# LED.net
KiCad netlist of a schematic drawn in EAGLE
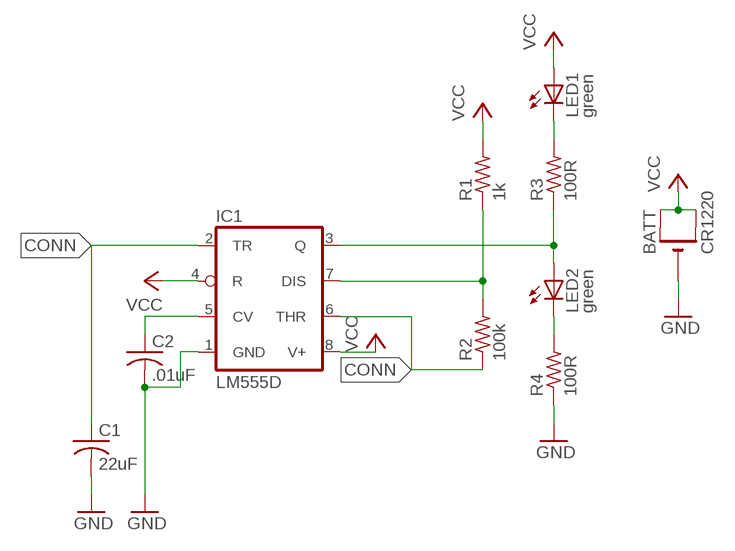
[diagram p0: schematic, sheet 1]

(export (version "E")
  (design (tool "Eeschema 10.0.6"))
  (components
    (comp (ref "BATT")
      (value "CR1220")
      (footprint "eagle-import:CR1220-SMD")
      (libsource (lib "eagle-import") (part "CR1220SMT"))
    )
    (comp (ref "C1")
      (value "22uF")
      (footprint "eagle-import:C0805")
      (fields (field (name "SPICEPREFIX") "C"))
      (libsource (lib "eagle-import") (part "C-USC0805"))
    )
    (comp (ref "C2")
      (value ".01uF")
      (footprint "eagle-import:C0805")
      (libsource (lib "eagle-import") (part "C-USC0805"))
    )
    (comp (ref "IC1")
      (value "LM555D")
      (footprint "eagle-import:SO08")
      (fields (field (name "SPICEPREFIX") "X"))
      (libsource (lib "eagle-import") (part "555DLM"))
    )
    (comp (ref "LED1")
      (value "green")
      (footprint "eagle-import:CHIPLED_0805")
      (libsource (lib "eagle-import") (part "LEDCHIPLED_0805"))
    )
    (comp (ref "LED2")
      (value "green")
      (footprint "eagle-import:CHIPLED_0805")
      (libsource (lib "eagle-import") (part "LEDCHIPLED_0805"))
    )
    (comp (ref "R1")
      (value "1k")
      (footprint "eagle-import:R0805")
      (libsource (lib "eagle-import") (part "R-US_R0805"))
    )
    (comp (ref "R2")
      (value "100k")
      (footprint "eagle-import:R0805")
      (libsource (lib "eagle-import") (part "R-US_R0805"))
    )
    (comp (ref "R3")
      (value "100R")
      (footprint "eagle-import:R0805")
      (libsource (lib "eagle-import") (part "R-US_R0805"))
    )
    (comp (ref "R4")
      (value "100R")
      (footprint "eagle-import:R0805")
      (libsource (lib "eagle-import") (part "R-US_R0805"))
    )
  )
  (nets
    (net (code "1") (name "CONN") (class "Default")
      (node (ref "C1") (pin "1") (pinfunction "1_1") (pintype "passive"))
      (node (ref "IC1") (pin "2") (pinfunction "TR_2") (pintype "input"))
      (node (ref "IC1") (pin "6") (pinfunction "THR_6") (pintype "input"))
      (node (ref "R2") (pin "1") (pinfunction "1_1") (pintype "passive"))
    )
    (net (code "2") (name "GND") (class "Default")
      (node (ref "BATT") (pin "-") (pinfunction "-_-") (pintype "passive"))
      (node (ref "C1") (pin "2") (pinfunction "2_2") (pintype "passive"))
      (node (ref "C2") (pin "2") (pinfunction "2_2") (pintype "passive"))
      (node (ref "IC1") (pin "1") (pinfunction "GND_1") (pintype "power_in"))
      (node (ref "R4") (pin "1") (pinfunction "1_1") (pintype "passive"))
    )
    (net (code "3") (name "Net-(IC1-CV)") (class "Default")
      (node (ref "C2") (pin "1") (pinfunction "1_1") (pintype "passive"))
      (node (ref "IC1") (pin "5") (pinfunction "CV_5") (pintype "input"))
    )
    (net (code "4") (name "Net-(IC1-DIS)") (class "Default")
      (node (ref "IC1") (pin "7") (pinfunction "DIS_7") (pintype "input"))
      (node (ref "R1") (pin "1") (pinfunction "1_1") (pintype "passive"))
      (node (ref "R2") (pin "2") (pinfunction "2_2") (pintype "passive"))
    )
    (net (code "5") (name "Net-(IC1-Q)") (class "Default")
      (node (ref "IC1") (pin "3") (pinfunction "Q_3") (pintype "output"))
      (node (ref "LED2") (pin "A") (pinfunction "A_A") (pintype "passive"))
      (node (ref "R3") (pin "1") (pinfunction "1_1") (pintype "passive"))
    )
    (net (code "6") (name "Net-(LED1-PadC)") (class "Default")
      (node (ref "LED1") (pin "C") (pinfunction "C_C") (pintype "passive"))
      (node (ref "R3") (pin "2") (pinfunction "2_2") (pintype "passive"))
    )
    (net (code "7") (name "Net-(LED2-PadC)") (class "Default")
      (node (ref "LED2") (pin "C") (pinfunction "C_C") (pintype "passive"))
      (node (ref "R4") (pin "2") (pinfunction "2_2") (pintype "passive"))
    )
    (net (code "8") (name "VCC") (class "Default")
      (node (ref "BATT") (pin "+$1") (pinfunction "+_+$1") (pintype "passive"))
      (node (ref "BATT") (pin "+$2") (pinfunction "+1_+$2") (pintype "passive"))
      (node (ref "IC1") (pin "4") (pinfunction "R_4") (pintype "input"))
      (node (ref "IC1") (pin "8") (pinfunction "V+_8") (pintype "power_in"))
      (node (ref "LED1") (pin "A") (pinfunction "A_A") (pintype "passive"))
      (node (ref "R1") (pin "2") (pinfunction "2_2") (pintype "passive"))
    )
  )
)
